# BoardA1-Changed_connectors.net
KiCad netlist of a schematic drawn in EAGLE
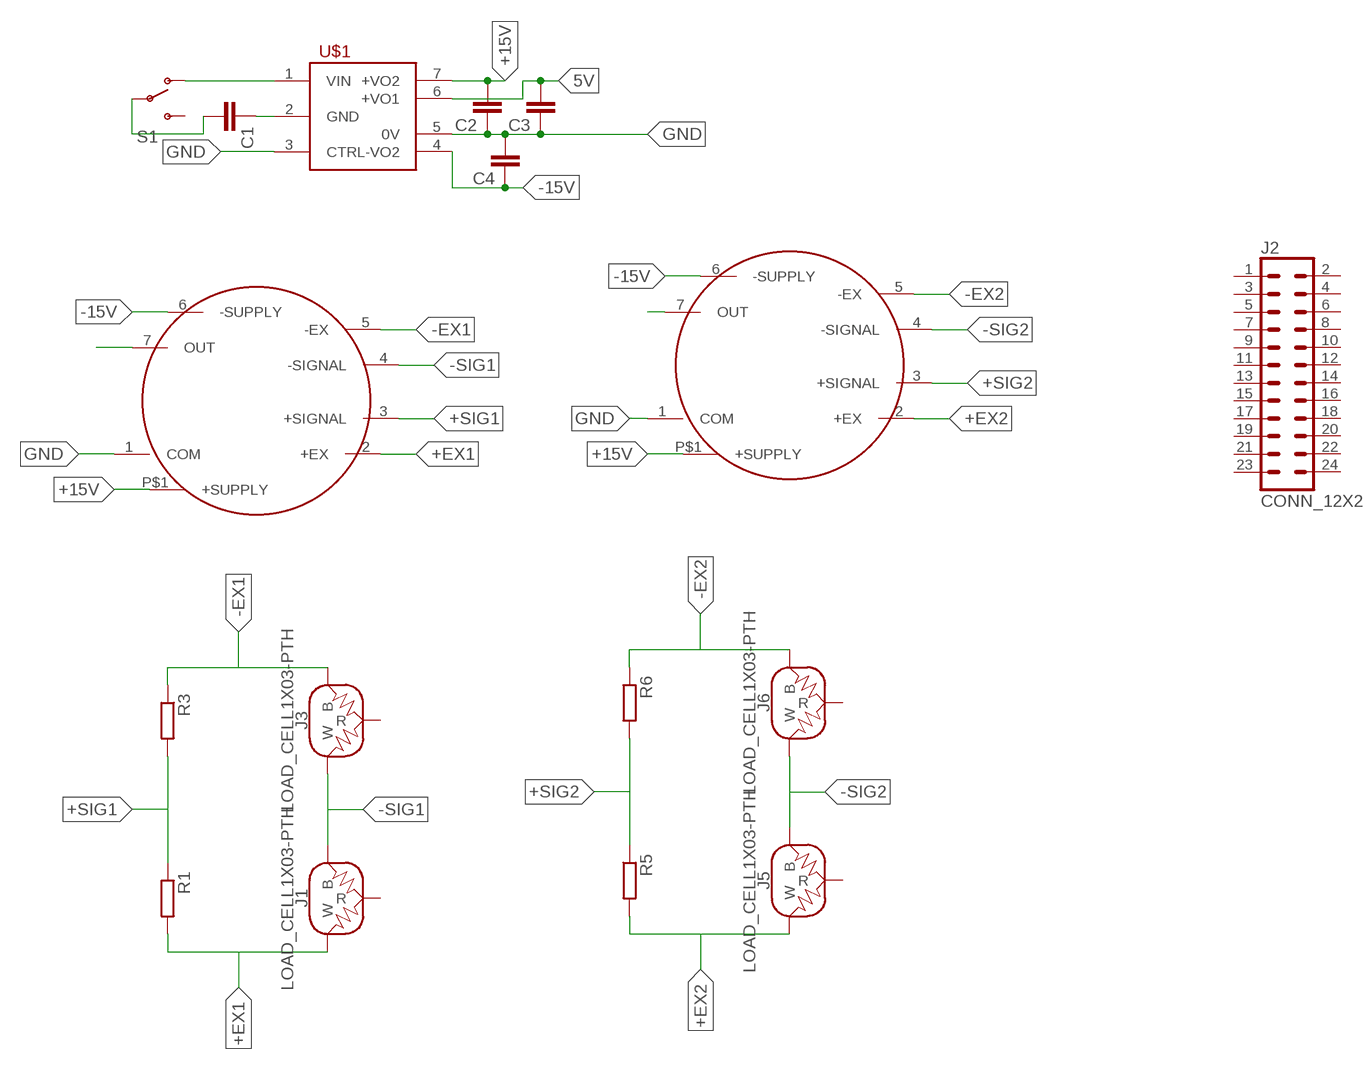
[diagram p0: schematic, sheet 1]

(export (version "E")
  (design (tool "Eeschema 10.0.6"))
  (components
    (comp (ref "C1")
      (value "CAP0805")
      (footprint "eagle-import:0805")
      (libsource (lib "eagle-import") (part "CAP0805"))
    )
    (comp (ref "C2")
      (value "CAP0805")
      (footprint "eagle-import:0805")
      (libsource (lib "eagle-import") (part "CAP0805"))
    )
    (comp (ref "C3")
      (value "CAP0805")
      (footprint "eagle-import:0805")
      (libsource (lib "eagle-import") (part "CAP0805"))
    )
    (comp (ref "C4")
      (value "CAP0805")
      (footprint "eagle-import:0805")
      (libsource (lib "eagle-import") (part "CAP0805"))
    )
    (comp (ref "J1")
      (value "LOAD_CELL1X03-PTH")
      (footprint "eagle-import:1X03")
      (libsource (lib "eagle-import") (part "LOAD_CELL1X03-PTH"))
    )
    (comp (ref "J2")
      (value "CONN_12X2")
      (footprint "eagle-import:2X12")
      (libsource (lib "eagle-import") (part "CONN_12X2"))
    )
    (comp (ref "J3")
      (value "LOAD_CELL1X03-PTH")
      (footprint "eagle-import:1X03")
      (libsource (lib "eagle-import") (part "LOAD_CELL1X03-PTH"))
    )
    (comp (ref "J5")
      (value "LOAD_CELL1X03-PTH")
      (footprint "eagle-import:1X03")
      (libsource (lib "eagle-import") (part "LOAD_CELL1X03-PTH"))
    )
    (comp (ref "J6")
      (value "LOAD_CELL1X03-PTH")
      (footprint "eagle-import:1X03")
      (libsource (lib "eagle-import") (part "LOAD_CELL1X03-PTH"))
    )
    (comp (ref "R1")
      (value "R0204/7")
      (footprint "eagle-import:0204_7")
      (libsource (lib "eagle-import") (part "R0204/7"))
    )
    (comp (ref "R3")
      (value "R0204/7")
      (footprint "eagle-import:0204_7")
      (libsource (lib "eagle-import") (part "R0204/7"))
    )
    (comp (ref "R5")
      (value "R0204/7")
      (footprint "eagle-import:0204_7")
      (libsource (lib "eagle-import") (part "R0204/7"))
    )
    (comp (ref "R6")
      (value "R0204/7")
      (footprint "eagle-import:0204_7")
      (libsource (lib "eagle-import") (part "R0204/7"))
    )
    (comp (ref "S1")
      (value "SWITCH-SPDTPTH")
      (footprint "eagle-import:SWITCH-SPDT")
      (libsource (lib "eagle-import") (part "SWITCH-SPDTPTH"))
    )
    (comp (ref "U$1")
      (value "DC-DC")
      (footprint "eagle-import:DC-DCCONVERTER")
      (libsource (lib "eagle-import") (part "DC-DC"))
    )
    (comp (ref "U$2")
      (value "ICA3H")
      (footprint "eagle-import:ICA3H")
      (libsource (lib "eagle-import") (part "ICA3H"))
    )
    (comp (ref "U$3")
      (value "ICA3H")
      (footprint "eagle-import:ICA3H")
      (libsource (lib "eagle-import") (part "ICA3H"))
    )
  )
  (nets
    (net (code "1") (name "+15V") (class "Default")
      (node (ref "C2") (pin "2") (pinfunction "2_2") (pintype "passive"))
      (node (ref "U$1") (pin "7") (pinfunction "+VO2_7") (pintype "bidirectional"))
      (node (ref "U$2") (pin "P$1") (pinfunction "+SUPPLY_P$1") (pintype "bidirectional"))
      (node (ref "U$3") (pin "P$1") (pinfunction "+SUPPLY_P$1") (pintype "bidirectional"))
    )
    (net (code "2") (name "+EX1") (class "Default")
      (node (ref "J1") (pin "2") (pinfunction "W_2") (pintype "passive"))
      (node (ref "R1") (pin "2") (pinfunction "2_2") (pintype "passive"))
      (node (ref "U$2") (pin "2") (pinfunction "+EX_2") (pintype "bidirectional"))
    )
    (net (code "3") (name "+EX2") (class "Default")
      (node (ref "J5") (pin "2") (pinfunction "W_2") (pintype "passive"))
      (node (ref "R5") (pin "2") (pinfunction "2_2") (pintype "passive"))
      (node (ref "U$3") (pin "2") (pinfunction "+EX_2") (pintype "bidirectional"))
    )
    (net (code "4") (name "+SIG1") (class "Default")
      (node (ref "R1") (pin "1") (pinfunction "1_1") (pintype "passive"))
      (node (ref "R3") (pin "2") (pinfunction "2_2") (pintype "passive"))
      (node (ref "U$2") (pin "3") (pinfunction "+SIGNAL_3") (pintype "bidirectional"))
    )
    (net (code "5") (name "+SIG2") (class "Default")
      (node (ref "R5") (pin "1") (pinfunction "1_1") (pintype "passive"))
      (node (ref "R6") (pin "2") (pinfunction "2_2") (pintype "passive"))
      (node (ref "U$3") (pin "3") (pinfunction "+SIGNAL_3") (pintype "bidirectional"))
    )
    (net (code "6") (name "-15V") (class "Default")
      (node (ref "C4") (pin "1") (pinfunction "1_1") (pintype "passive"))
      (node (ref "U$1") (pin "4") (pinfunction "-VO2_4") (pintype "bidirectional"))
      (node (ref "U$2") (pin "6") (pinfunction "-SUPPLY_6") (pintype "bidirectional"))
      (node (ref "U$3") (pin "6") (pinfunction "-SUPPLY_6") (pintype "bidirectional"))
    )
    (net (code "7") (name "-EX1") (class "Default")
      (node (ref "J3") (pin "1") (pinfunction "B_1") (pintype "passive"))
      (node (ref "R3") (pin "1") (pinfunction "1_1") (pintype "passive"))
      (node (ref "U$2") (pin "5") (pinfunction "-EX_5") (pintype "bidirectional"))
    )
    (net (code "8") (name "-EX2") (class "Default")
      (node (ref "J6") (pin "1") (pinfunction "B_1") (pintype "passive"))
      (node (ref "R6") (pin "1") (pinfunction "1_1") (pintype "passive"))
      (node (ref "U$3") (pin "5") (pinfunction "-EX_5") (pintype "bidirectional"))
    )
    (net (code "9") (name "-SIG1") (class "Default")
      (node (ref "J1") (pin "1") (pinfunction "B_1") (pintype "passive"))
      (node (ref "J3") (pin "2") (pinfunction "W_2") (pintype "passive"))
      (node (ref "U$2") (pin "4") (pinfunction "-SIGNAL_4") (pintype "bidirectional"))
    )
    (net (code "10") (name "-SIG2") (class "Default")
      (node (ref "J5") (pin "1") (pinfunction "B_1") (pintype "passive"))
      (node (ref "J6") (pin "2") (pinfunction "W_2") (pintype "passive"))
      (node (ref "U$3") (pin "4") (pinfunction "-SIGNAL_4") (pintype "bidirectional"))
    )
    (net (code "11") (name "5V") (class "Default")
      (node (ref "C3") (pin "2") (pinfunction "2_2") (pintype "passive"))
      (node (ref "U$1") (pin "6") (pinfunction "+VO1_6") (pintype "bidirectional"))
    )
    (net (code "12") (name "GND") (class "Default")
      (node (ref "C2") (pin "1") (pinfunction "1_1") (pintype "passive"))
      (node (ref "C3") (pin "1") (pinfunction "1_1") (pintype "passive"))
      (node (ref "C4") (pin "2") (pinfunction "2_2") (pintype "passive"))
      (node (ref "U$1") (pin "3") (pinfunction "CTRL_3") (pintype "bidirectional"))
      (node (ref "U$1") (pin "5") (pinfunction "0V_5") (pintype "bidirectional"))
      (node (ref "U$2") (pin "1") (pinfunction "COM_1") (pintype "bidirectional"))
      (node (ref "U$3") (pin "1") (pinfunction "COM_1") (pintype "bidirectional"))
    )
    (net (code "13") (name "Net-(S1-O)") (class "Default")
      (node (ref "S1") (pin "1") (pinfunction "O_1") (pintype "passive"))
      (node (ref "U$1") (pin "1") (pinfunction "VIN_1") (pintype "bidirectional"))
    )
    (net (code "14") (name "Net-(S1-P)") (class "Default")
      (node (ref "C1") (pin "2") (pinfunction "2_2") (pintype "passive"))
      (node (ref "S1") (pin "2") (pinfunction "P_2") (pintype "passive"))
    )
    (net (code "15") (name "Net-(U$1-GND)") (class "Default")
      (node (ref "C1") (pin "1") (pinfunction "1_1") (pintype "passive"))
      (node (ref "U$1") (pin "2") (pinfunction "GND_2") (pintype "bidirectional"))
    )
    (net (code "16") (name "unconnected-(J1-R-Pad3)") (class "Default")
      (node (ref "J1") (pin "3") (pinfunction "R_3") (pintype "passive"))
    )
    (net (code "17") (name "unconnected-(J2-Pad1)") (class "Default")
      (node (ref "J2") (pin "1") (pinfunction "1_1") (pintype "passive"))
    )
    (net (code "18") (name "unconnected-(J2-Pad2)") (class "Default")
      (node (ref "J2") (pin "2") (pinfunction "2_2") (pintype "passive"))
    )
    (net (code "19") (name "unconnected-(J2-Pad3)") (class "Default")
      (node (ref "J2") (pin "3") (pinfunction "3_3") (pintype "passive"))
    )
    (net (code "20") (name "unconnected-(J2-Pad4)") (class "Default")
      (node (ref "J2") (pin "4") (pinfunction "4_4") (pintype "passive"))
    )
    (net (code "21") (name "unconnected-(J2-Pad5)") (class "Default")
      (node (ref "J2") (pin "5") (pinfunction "5_5") (pintype "passive"))
    )
    (net (code "22") (name "unconnected-(J2-Pad6)") (class "Default")
      (node (ref "J2") (pin "6") (pinfunction "6_6") (pintype "passive"))
    )
    (net (code "23") (name "unconnected-(J2-Pad7)") (class "Default")
      (node (ref "J2") (pin "7") (pinfunction "7_7") (pintype "passive"))
    )
    (net (code "24") (name "unconnected-(J2-Pad8)") (class "Default")
      (node (ref "J2") (pin "8") (pinfunction "8_8") (pintype "passive"))
    )
    (net (code "25") (name "unconnected-(J2-Pad9)") (class "Default")
      (node (ref "J2") (pin "9") (pinfunction "9_9") (pintype "passive"))
    )
    (net (code "26") (name "unconnected-(J2-Pad10)") (class "Default")
      (node (ref "J2") (pin "10") (pinfunction "10_10") (pintype "passive"))
    )
    (net (code "27") (name "unconnected-(J2-Pad11)") (class "Default")
      (node (ref "J2") (pin "11") (pinfunction "11_11") (pintype "passive"))
    )
    (net (code "28") (name "unconnected-(J2-Pad12)") (class "Default")
      (node (ref "J2") (pin "12") (pinfunction "12_12") (pintype "passive"))
    )
    (net (code "29") (name "unconnected-(J2-Pad13)") (class "Default")
      (node (ref "J2") (pin "13") (pinfunction "13_13") (pintype "passive"))
    )
    (net (code "30") (name "unconnected-(J2-Pad14)") (class "Default")
      (node (ref "J2") (pin "14") (pinfunction "14_14") (pintype "passive"))
    )
    (net (code "31") (name "unconnected-(J2-Pad15)") (class "Default")
      (node (ref "J2") (pin "15") (pinfunction "15_15") (pintype "passive"))
    )
    (net (code "32") (name "unconnected-(J2-Pad16)") (class "Default")
      (node (ref "J2") (pin "16") (pinfunction "16_16") (pintype "passive"))
    )
    (net (code "33") (name "unconnected-(J2-Pad17)") (class "Default")
      (node (ref "J2") (pin "17") (pinfunction "17_17") (pintype "passive"))
    )
    (net (code "34") (name "unconnected-(J2-Pad18)") (class "Default")
      (node (ref "J2") (pin "18") (pinfunction "18_18") (pintype "passive"))
    )
    (net (code "35") (name "unconnected-(J2-Pad19)") (class "Default")
      (node (ref "J2") (pin "19") (pinfunction "19_19") (pintype "passive"))
    )
    (net (code "36") (name "unconnected-(J2-Pad20)") (class "Default")
      (node (ref "J2") (pin "20") (pinfunction "20_20") (pintype "passive"))
    )
    (net (code "37") (name "unconnected-(J2-Pad21)") (class "Default")
      (node (ref "J2") (pin "21") (pinfunction "21_21") (pintype "passive"))
    )
    (net (code "38") (name "unconnected-(J2-Pad22)") (class "Default")
      (node (ref "J2") (pin "22") (pinfunction "22_22") (pintype "passive"))
    )
    (net (code "39") (name "unconnected-(J2-Pad23)") (class "Default")
      (node (ref "J2") (pin "23") (pinfunction "23_23") (pintype "passive"))
    )
    (net (code "40") (name "unconnected-(J2-Pad24)") (class "Default")
      (node (ref "J2") (pin "24") (pinfunction "24_24") (pintype "passive"))
    )
    (net (code "41") (name "unconnected-(J3-R-Pad3)") (class "Default")
      (node (ref "J3") (pin "3") (pinfunction "R_3") (pintype "passive"))
    )
    (net (code "42") (name "unconnected-(J5-R-Pad3)") (class "Default")
      (node (ref "J5") (pin "3") (pinfunction "R_3") (pintype "passive"))
    )
    (net (code "43") (name "unconnected-(J6-R-Pad3)") (class "Default")
      (node (ref "J6") (pin "3") (pinfunction "R_3") (pintype "passive"))
    )
    (net (code "44") (name "unconnected-(S1-S-Pad3)") (class "Default")
      (node (ref "S1") (pin "3") (pinfunction "S_3") (pintype "passive"))
    )
    (net (code "45") (name "unconnected-(U$2-OUT-Pad7)") (class "Default")
      (node (ref "U$2") (pin "7") (pinfunction "OUT_7") (pintype "bidirectional"))
    )
    (net (code "46") (name "unconnected-(U$3-OUT-Pad7)") (class "Default")
      (node (ref "U$3") (pin "7") (pinfunction "OUT_7") (pintype "bidirectional"))
    )
  )
)
